# lpc1347.net
KiCad netlist of a schematic drawn in EAGLE
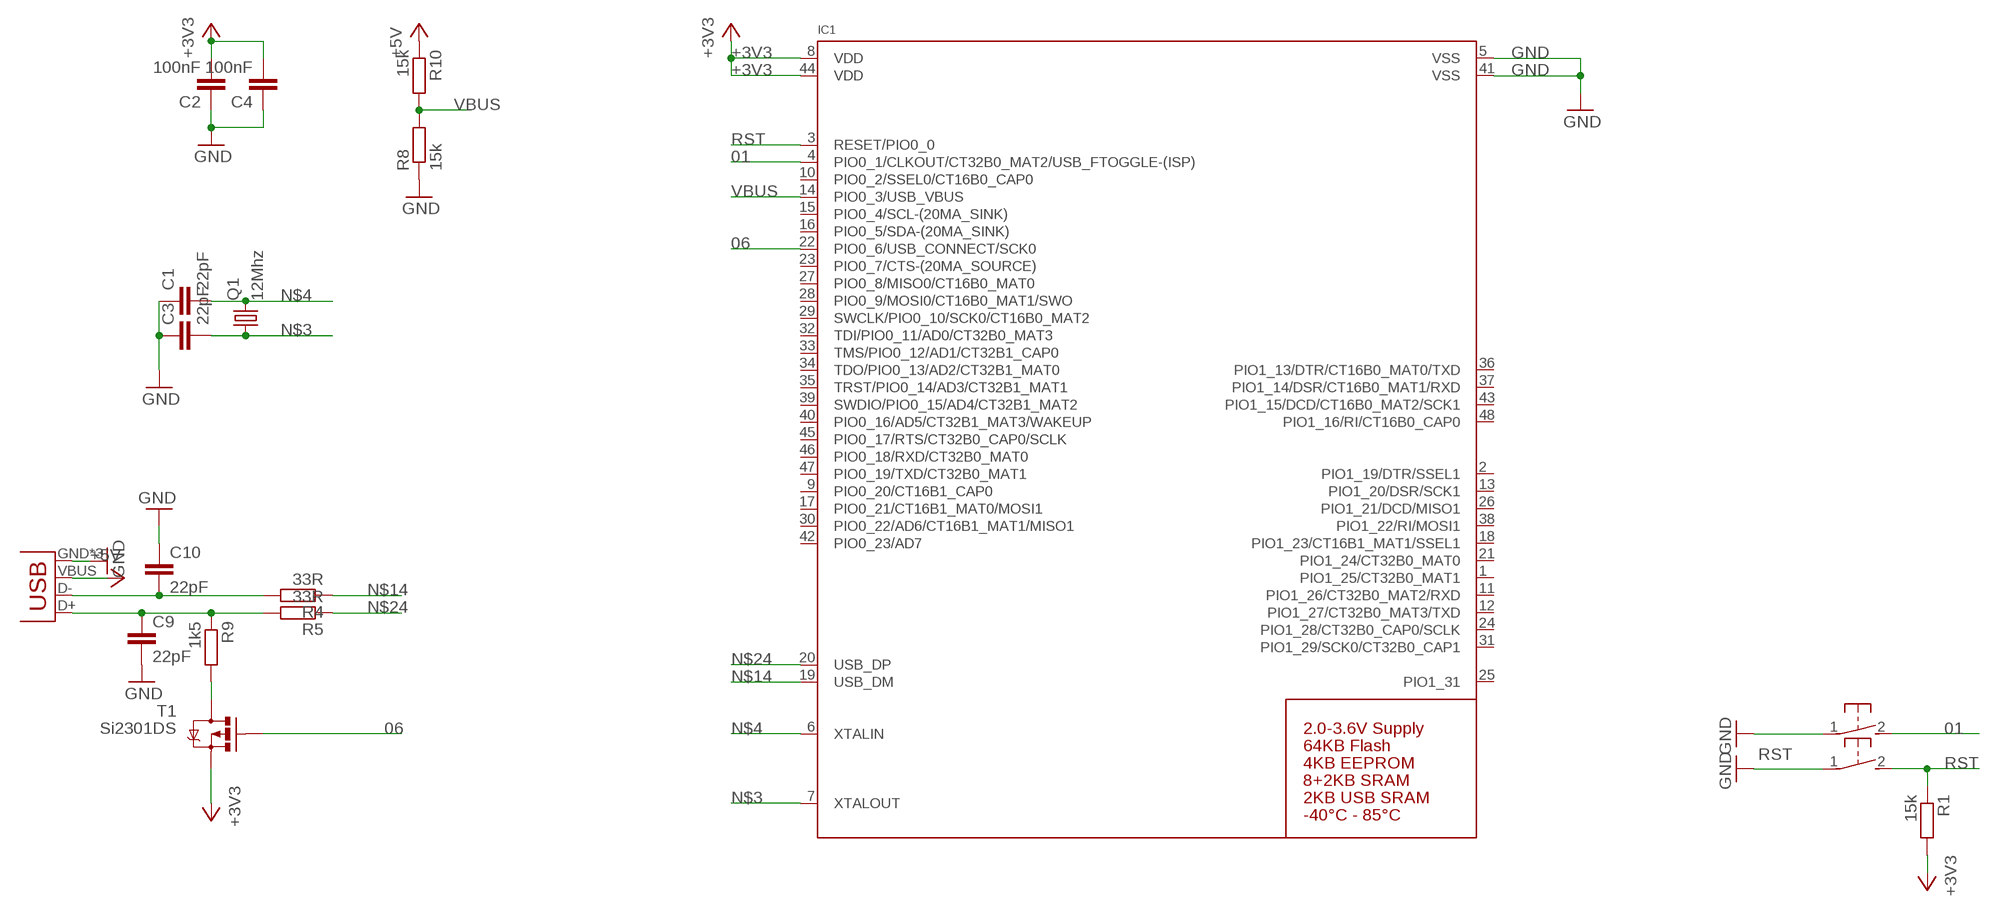
[diagram p0: schematic, sheet 1]

(export (version "E")
  (design (tool "Eeschema 10.0.6"))
  (components
    (comp (ref "BL/SW2")
      (value "SWITCH_MCTAEF")
      (footprint "eagle-import:SWITCH_MCTAEF")
      (libsource (lib "eagle-import") (part "SWITCH_MCTAEF"))
    )
    (comp (ref "C1")
      (value "22pF")
      (footprint "eagle-import:C0402")
      (libsource (lib "eagle-import") (part "C-EUC0402"))
    )
    (comp (ref "C2")
      (value "100nF")
      (footprint "eagle-import:C0402")
      (libsource (lib "eagle-import") (part "C-EUC0402"))
    )
    (comp (ref "C3")
      (value "22pF")
      (footprint "eagle-import:C0402")
      (libsource (lib "eagle-import") (part "C-EUC0402"))
    )
    (comp (ref "C4")
      (value "100nF")
      (footprint "eagle-import:C0402")
      (libsource (lib "eagle-import") (part "C-EUC0402"))
    )
    (comp (ref "C9")
      (value "22pF")
      (footprint "eagle-import:C0402")
      (libsource (lib "eagle-import") (part "C-EUC0402"))
    )
    (comp (ref "C10")
      (value "22pF")
      (footprint "eagle-import:C0402")
      (libsource (lib "eagle-import") (part "C-EUC0402"))
    )
    (comp (ref "IC1")
      (value "LPC1347_QFP48")
      (footprint "eagle-import:LQFP48")
      (libsource (lib "eagle-import") (part "LPC1347_QFP48"))
    )
    (comp (ref "Q1")
      (value "12Mhz")
      (footprint "eagle-import:MT")
      (libsource (lib "eagle-import") (part "MT-OSCILLATOR"))
    )
    (comp (ref "R1")
      (value "15k")
      (footprint "eagle-import:R0402")
      (libsource (lib "eagle-import") (part "R-EU_R0402"))
    )
    (comp (ref "R4")
      (value "33R")
      (footprint "eagle-import:R0402")
      (libsource (lib "eagle-import") (part "R-EU_R0402"))
    )
    (comp (ref "R5")
      (value "33R")
      (footprint "eagle-import:R0402")
      (libsource (lib "eagle-import") (part "R-EU_R0402"))
    )
    (comp (ref "R8")
      (value "15k")
      (footprint "eagle-import:R0402")
      (libsource (lib "eagle-import") (part "R-EU_R0402"))
    )
    (comp (ref "R9")
      (value "1k5")
      (footprint "eagle-import:R0402")
      (libsource (lib "eagle-import") (part "R-EU_R0402"))
    )
    (comp (ref "R10")
      (value "15k")
      (footprint "eagle-import:R0402")
      (libsource (lib "eagle-import") (part "R-EU_R0402"))
    )
    (comp (ref "RST")
      (value "SWITCH_MCTAEF")
      (footprint "eagle-import:SWITCH_MCTAEF")
      (libsource (lib "eagle-import") (part "SWITCH_MCTAEF"))
    )
    (comp (ref "T1")
      (value "Si2301DS")
      (footprint "eagle-import:SOT23")
      (libsource (lib "eagle-import") (part "MOSFET-PCHANNEL"))
    )
    (comp (ref "X1")
      (value "USB-MICROB")
      (footprint "eagle-import:USB-MICROB")
      (libsource (lib "eagle-import") (part "USB-MICROB"))
    )
  )
  (nets
    (net (code "1") (name "+3V3") (class "Default")
      (node (ref "C2") (pin "2") (pinfunction "2_2") (pintype "passive"))
      (node (ref "C4") (pin "2") (pinfunction "2_2") (pintype "passive"))
      (node (ref "IC1") (pin "44") (pinfunction "VDD_44") (pintype "power_in"))
      (node (ref "IC1") (pin "8") (pinfunction "VDD_8") (pintype "power_in"))
      (node (ref "R1") (pin "2") (pinfunction "2_2") (pintype "passive"))
      (node (ref "T1") (pin "2") (pinfunction "S_2") (pintype "passive"))
    )
    (net (code "2") (name "+5V") (class "Default")
      (node (ref "R10") (pin "1") (pinfunction "1_1") (pintype "passive"))
      (node (ref "X1") (pin "VBUS") (pinfunction "VBUS_VBUS") (pintype "bidirectional"))
    )
    (net (code "3") (name "/01") (class "Default")
      (node (ref "BL/SW2") (pin "2") (pinfunction "2_2") (pintype "passive"))
      (node (ref "IC1") (pin "4") (pinfunction "PIO0_1/CLKOUT/CT32B0_MAT2/USB_FTOGGLE-(ISP)_4") (pintype "bidirectional"))
    )
    (net (code "4") (name "/06") (class "Default")
      (node (ref "IC1") (pin "22") (pinfunction "PIO0_6/USB_CONNECT/SCK0_22") (pintype "bidirectional"))
      (node (ref "T1") (pin "1") (pinfunction "G_1") (pintype "passive"))
    )
    (net (code "5") (name "/N$3") (class "Default")
      (node (ref "C3") (pin "2") (pinfunction "2_2") (pintype "passive"))
      (node (ref "IC1") (pin "7") (pinfunction "XTALOUT_7") (pintype "bidirectional"))
      (node (ref "Q1") (pin "1") (pinfunction "1_1") (pintype "passive"))
    )
    (net (code "6") (name "/N$4") (class "Default")
      (node (ref "C1") (pin "2") (pinfunction "2_2") (pintype "passive"))
      (node (ref "IC1") (pin "6") (pinfunction "XTALIN_6") (pintype "bidirectional"))
      (node (ref "Q1") (pin "3") (pinfunction "2_3") (pintype "passive"))
    )
    (net (code "7") (name "/N$14") (class "Default")
      (node (ref "IC1") (pin "19") (pinfunction "USB_DM_19") (pintype "bidirectional"))
      (node (ref "R4") (pin "1") (pinfunction "1_1") (pintype "passive"))
    )
    (net (code "8") (name "/N$24") (class "Default")
      (node (ref "IC1") (pin "20") (pinfunction "USB_DP_20") (pintype "bidirectional"))
      (node (ref "R5") (pin "1") (pinfunction "1_1") (pintype "passive"))
    )
    (net (code "9") (name "/RST") (class "Default")
      (node (ref "IC1") (pin "3") (pinfunction "RESET/PIO0_0_3") (pintype "bidirectional"))
      (node (ref "R1") (pin "1") (pinfunction "1_1") (pintype "passive"))
      (node (ref "RST") (pin "2") (pinfunction "2_2") (pintype "passive"))
    )
    (net (code "10") (name "/VBUS") (class "Default")
      (node (ref "IC1") (pin "14") (pinfunction "PIO0_3/USB_VBUS_14") (pintype "bidirectional"))
      (node (ref "R10") (pin "2") (pinfunction "2_2") (pintype "passive"))
      (node (ref "R8") (pin "2") (pinfunction "2_2") (pintype "passive"))
    )
    (net (code "11") (name "GND") (class "Default")
      (node (ref "BL/SW2") (pin "1") (pinfunction "1_1") (pintype "passive"))
      (node (ref "C1") (pin "1") (pinfunction "1_1") (pintype "passive"))
      (node (ref "C10") (pin "1") (pinfunction "1_1") (pintype "passive"))
      (node (ref "C2") (pin "1") (pinfunction "1_1") (pintype "passive"))
      (node (ref "C3") (pin "1") (pinfunction "1_1") (pintype "passive"))
      (node (ref "C4") (pin "1") (pinfunction "1_1") (pintype "passive"))
      (node (ref "C9") (pin "2") (pinfunction "2_2") (pintype "passive"))
      (node (ref "IC1") (pin "41") (pinfunction "VSS_41") (pintype "power_in"))
      (node (ref "IC1") (pin "5") (pinfunction "VSS_5") (pintype "power_in"))
      (node (ref "R8") (pin "1") (pinfunction "1_1") (pintype "passive"))
      (node (ref "RST") (pin "1") (pinfunction "1_1") (pintype "passive"))
      (node (ref "X1") (pin "GND") (pinfunction "GND_GND") (pintype "bidirectional"))
      (node (ref "X1") (pin "MT1") (pinfunction "GND_MT1") (pintype "bidirectional"))
      (node (ref "X1") (pin "MT2") (pinfunction "GND_MT2") (pintype "bidirectional"))
    )
    (net (code "12") (name "Net-(C9-Pad1)") (class "Default")
      (node (ref "C9") (pin "1") (pinfunction "1_1") (pintype "passive"))
      (node (ref "R5") (pin "2") (pinfunction "2_2") (pintype "passive"))
      (node (ref "R9") (pin "1") (pinfunction "1_1") (pintype "passive"))
      (node (ref "X1") (pin "D+") (pinfunction "D+_D+") (pintype "bidirectional"))
    )
    (net (code "13") (name "Net-(C10-Pad2)") (class "Default")
      (node (ref "C10") (pin "2") (pinfunction "2_2") (pintype "passive"))
      (node (ref "R4") (pin "2") (pinfunction "2_2") (pintype "passive"))
      (node (ref "X1") (pin "D-") (pinfunction "D-_D-") (pintype "bidirectional"))
    )
    (net (code "14") (name "Net-(T1-D)") (class "Default")
      (node (ref "R9") (pin "2") (pinfunction "2_2") (pintype "passive"))
      (node (ref "T1") (pin "3") (pinfunction "D_3") (pintype "passive"))
    )
    (net (code "15") (name "unconnected-(IC1-PIO0_2{slash}SSEL0{slash}CT16B0_CAP0-Pad10)") (class "Default")
      (node (ref "IC1") (pin "10") (pinfunction "PIO0_2/SSEL0/CT16B0_CAP0_10") (pintype "bidirectional"))
    )
    (net (code "16") (name "unconnected-(IC1-PIO0_4{slash}SCL-(20MA_SINK)-Pad15)") (class "Default")
      (node (ref "IC1") (pin "15") (pinfunction "PIO0_4/SCL-(20MA_SINK)_15") (pintype "bidirectional"))
    )
    (net (code "17") (name "unconnected-(IC1-PIO0_5{slash}SDA-(20MA_SINK)-Pad16)") (class "Default")
      (node (ref "IC1") (pin "16") (pinfunction "PIO0_5/SDA-(20MA_SINK)_16") (pintype "bidirectional"))
    )
    (net (code "18") (name "unconnected-(IC1-PIO0_7{slash}CTS-(20MA_SOURCE)-Pad23)") (class "Default")
      (node (ref "IC1") (pin "23") (pinfunction "PIO0_7/CTS-(20MA_SOURCE)_23") (pintype "bidirectional"))
    )
    (net (code "19") (name "unconnected-(IC1-PIO0_8{slash}MISO0{slash}CT16B0_MAT0-Pad27)") (class "Default")
      (node (ref "IC1") (pin "27") (pinfunction "PIO0_8/MISO0/CT16B0_MAT0_27") (pintype "bidirectional"))
    )
    (net (code "20") (name "unconnected-(IC1-PIO0_9{slash}MOSI0{slash}CT16B0_MAT1{slash}SWO-Pad28)") (class "Default")
      (node (ref "IC1") (pin "28") (pinfunction "PIO0_9/MOSI0/CT16B0_MAT1/SWO_28") (pintype "bidirectional"))
    )
    (net (code "21") (name "unconnected-(IC1-PIO0_16{slash}AD5{slash}CT32B1_MAT3{slash}WAKEUP-Pad40)") (class "Default")
      (node (ref "IC1") (pin "40") (pinfunction "PIO0_16/AD5/CT32B1_MAT3/WAKEUP_40") (pintype "bidirectional"))
    )
    (net (code "22") (name "unconnected-(IC1-PIO0_17{slash}RTS{slash}CT32B0_CAP0{slash}SCLK-Pad45)") (class "Default")
      (node (ref "IC1") (pin "45") (pinfunction "PIO0_17/RTS/CT32B0_CAP0/SCLK_45") (pintype "bidirectional"))
    )
    (net (code "23") (name "unconnected-(IC1-PIO0_18{slash}RXD{slash}CT32B0_MAT0-Pad46)") (class "Default")
      (node (ref "IC1") (pin "46") (pinfunction "PIO0_18/RXD/CT32B0_MAT0_46") (pintype "bidirectional"))
    )
    (net (code "24") (name "unconnected-(IC1-PIO0_19{slash}TXD{slash}CT32B0_MAT1-Pad47)") (class "Default")
      (node (ref "IC1") (pin "47") (pinfunction "PIO0_19/TXD/CT32B0_MAT1_47") (pintype "bidirectional"))
    )
    (net (code "25") (name "unconnected-(IC1-PIO0_20{slash}CT16B1_CAP0-Pad9)") (class "Default")
      (node (ref "IC1") (pin "9") (pinfunction "PIO0_20/CT16B1_CAP0_9") (pintype "bidirectional"))
    )
    (net (code "26") (name "unconnected-(IC1-PIO0_21{slash}CT16B1_MAT0{slash}MOSI1-Pad17)") (class "Default")
      (node (ref "IC1") (pin "17") (pinfunction "PIO0_21/CT16B1_MAT0/MOSI1_17") (pintype "bidirectional"))
    )
    (net (code "27") (name "unconnected-(IC1-PIO0_22{slash}AD6{slash}CT16B1_MAT1{slash}MISO1-Pad30)") (class "Default")
      (node (ref "IC1") (pin "30") (pinfunction "PIO0_22/AD6/CT16B1_MAT1/MISO1_30") (pintype "bidirectional"))
    )
    (net (code "28") (name "unconnected-(IC1-PIO0_23{slash}AD7-Pad42)") (class "Default")
      (node (ref "IC1") (pin "42") (pinfunction "PIO0_23/AD7_42") (pintype "bidirectional"))
    )
    (net (code "29") (name "unconnected-(IC1-PIO1_13{slash}DTR{slash}CT16B0_MAT0{slash}TXD-Pad36)") (class "Default")
      (node (ref "IC1") (pin "36") (pinfunction "PIO1_13/DTR/CT16B0_MAT0/TXD_36") (pintype "bidirectional"))
    )
    (net (code "30") (name "unconnected-(IC1-PIO1_14{slash}DSR{slash}CT16B0_MAT1{slash}RXD-Pad37)") (class "Default")
      (node (ref "IC1") (pin "37") (pinfunction "PIO1_14/DSR/CT16B0_MAT1/RXD_37") (pintype "bidirectional"))
    )
    (net (code "31") (name "unconnected-(IC1-PIO1_15{slash}DCD{slash}CT16B0_MAT2{slash}SCK1-Pad43)") (class "Default")
      (node (ref "IC1") (pin "43") (pinfunction "PIO1_15/DCD/CT16B0_MAT2/SCK1_43") (pintype "bidirectional"))
    )
    (net (code "32") (name "unconnected-(IC1-PIO1_16{slash}RI{slash}CT16B0_CAP0-Pad48)") (class "Default")
      (node (ref "IC1") (pin "48") (pinfunction "PIO1_16/RI/CT16B0_CAP0_48") (pintype "bidirectional"))
    )
    (net (code "33") (name "unconnected-(IC1-PIO1_19{slash}DTR{slash}SSEL1-Pad2)") (class "Default")
      (node (ref "IC1") (pin "2") (pinfunction "PIO1_19/DTR/SSEL1_2") (pintype "bidirectional"))
    )
    (net (code "34") (name "unconnected-(IC1-PIO1_20{slash}DSR{slash}SCK1-Pad13)") (class "Default")
      (node (ref "IC1") (pin "13") (pinfunction "PIO1_20/DSR/SCK1_13") (pintype "bidirectional"))
    )
    (net (code "35") (name "unconnected-(IC1-PIO1_21{slash}DCD{slash}MISO1-Pad26)") (class "Default")
      (node (ref "IC1") (pin "26") (pinfunction "PIO1_21/DCD/MISO1_26") (pintype "bidirectional"))
    )
    (net (code "36") (name "unconnected-(IC1-PIO1_22{slash}RI{slash}MOSI1-Pad38)") (class "Default")
      (node (ref "IC1") (pin "38") (pinfunction "PIO1_22/RI/MOSI1_38") (pintype "bidirectional"))
    )
    (net (code "37") (name "unconnected-(IC1-PIO1_23{slash}CT16B1_MAT1{slash}SSEL1-Pad18)") (class "Default")
      (node (ref "IC1") (pin "18") (pinfunction "PIO1_23/CT16B1_MAT1/SSEL1_18") (pintype "bidirectional"))
    )
    (net (code "38") (name "unconnected-(IC1-PIO1_24{slash}CT32B0_MAT0-Pad21)") (class "Default")
      (node (ref "IC1") (pin "21") (pinfunction "PIO1_24/CT32B0_MAT0_21") (pintype "bidirectional"))
    )
    (net (code "39") (name "unconnected-(IC1-PIO1_25{slash}CT32B0_MAT1-Pad1)") (class "Default")
      (node (ref "IC1") (pin "1") (pinfunction "PIO1_25/CT32B0_MAT1_1") (pintype "bidirectional"))
    )
    (net (code "40") (name "unconnected-(IC1-PIO1_26{slash}CT32B0_MAT2{slash}RXD-Pad11)") (class "Default")
      (node (ref "IC1") (pin "11") (pinfunction "PIO1_26/CT32B0_MAT2/RXD_11") (pintype "bidirectional"))
    )
    (net (code "41") (name "unconnected-(IC1-PIO1_27{slash}CT32B0_MAT3{slash}TXD-Pad12)") (class "Default")
      (node (ref "IC1") (pin "12") (pinfunction "PIO1_27/CT32B0_MAT3/TXD_12") (pintype "bidirectional"))
    )
    (net (code "42") (name "unconnected-(IC1-PIO1_28{slash}CT32B0_CAP0{slash}SCLK-Pad24)") (class "Default")
      (node (ref "IC1") (pin "24") (pinfunction "PIO1_28/CT32B0_CAP0/SCLK_24") (pintype "bidirectional"))
    )
    (net (code "43") (name "unconnected-(IC1-PIO1_29{slash}SCK0{slash}CT32B0_CAP1-Pad31)") (class "Default")
      (node (ref "IC1") (pin "31") (pinfunction "PIO1_29/SCK0/CT32B0_CAP1_31") (pintype "bidirectional"))
    )
    (net (code "44") (name "unconnected-(IC1-PIO1_31-Pad25)") (class "Default")
      (node (ref "IC1") (pin "25") (pinfunction "PIO1_31_25") (pintype "bidirectional"))
    )
    (net (code "45") (name "unconnected-(IC1-SWCLK{slash}PIO0_10{slash}SCK0{slash}CT16B0_MAT2-Pad29)") (class "Default")
      (node (ref "IC1") (pin "29") (pinfunction "SWCLK/PIO0_10/SCK0/CT16B0_MAT2_29") (pintype "bidirectional"))
    )
    (net (code "46") (name "unconnected-(IC1-SWDIO{slash}PIO0_15{slash}AD4{slash}CT32B1_MAT2-Pad39)") (class "Default")
      (node (ref "IC1") (pin "39") (pinfunction "SWDIO/PIO0_15/AD4/CT32B1_MAT2_39") (pintype "bidirectional"))
    )
    (net (code "47") (name "unconnected-(IC1-TDI{slash}PIO0_11{slash}AD0{slash}CT32B0_MAT3-Pad32)") (class "Default")
      (node (ref "IC1") (pin "32") (pinfunction "TDI/PIO0_11/AD0/CT32B0_MAT3_32") (pintype "bidirectional"))
    )
    (net (code "48") (name "unconnected-(IC1-TDO{slash}PIO0_13{slash}AD2{slash}CT32B1_MAT0-Pad34)") (class "Default")
      (node (ref "IC1") (pin "34") (pinfunction "TDO/PIO0_13/AD2/CT32B1_MAT0_34") (pintype "bidirectional"))
    )
    (net (code "49") (name "unconnected-(IC1-TMS{slash}PIO0_12{slash}AD1{slash}CT32B1_CAP0-Pad33)") (class "Default")
      (node (ref "IC1") (pin "33") (pinfunction "TMS/PIO0_12/AD1/CT32B1_CAP0_33") (pintype "bidirectional"))
    )
    (net (code "50") (name "unconnected-(IC1-TRST{slash}PIO0_14{slash}AD3{slash}CT32B1_MAT1-Pad35)") (class "Default")
      (node (ref "IC1") (pin "35") (pinfunction "TRST/PIO0_14/AD3/CT32B1_MAT1_35") (pintype "bidirectional"))
    )
  )
)
